# tinyduino-breakout-mk-4_0.net
KiCad netlist of a schematic drawn in EAGLE
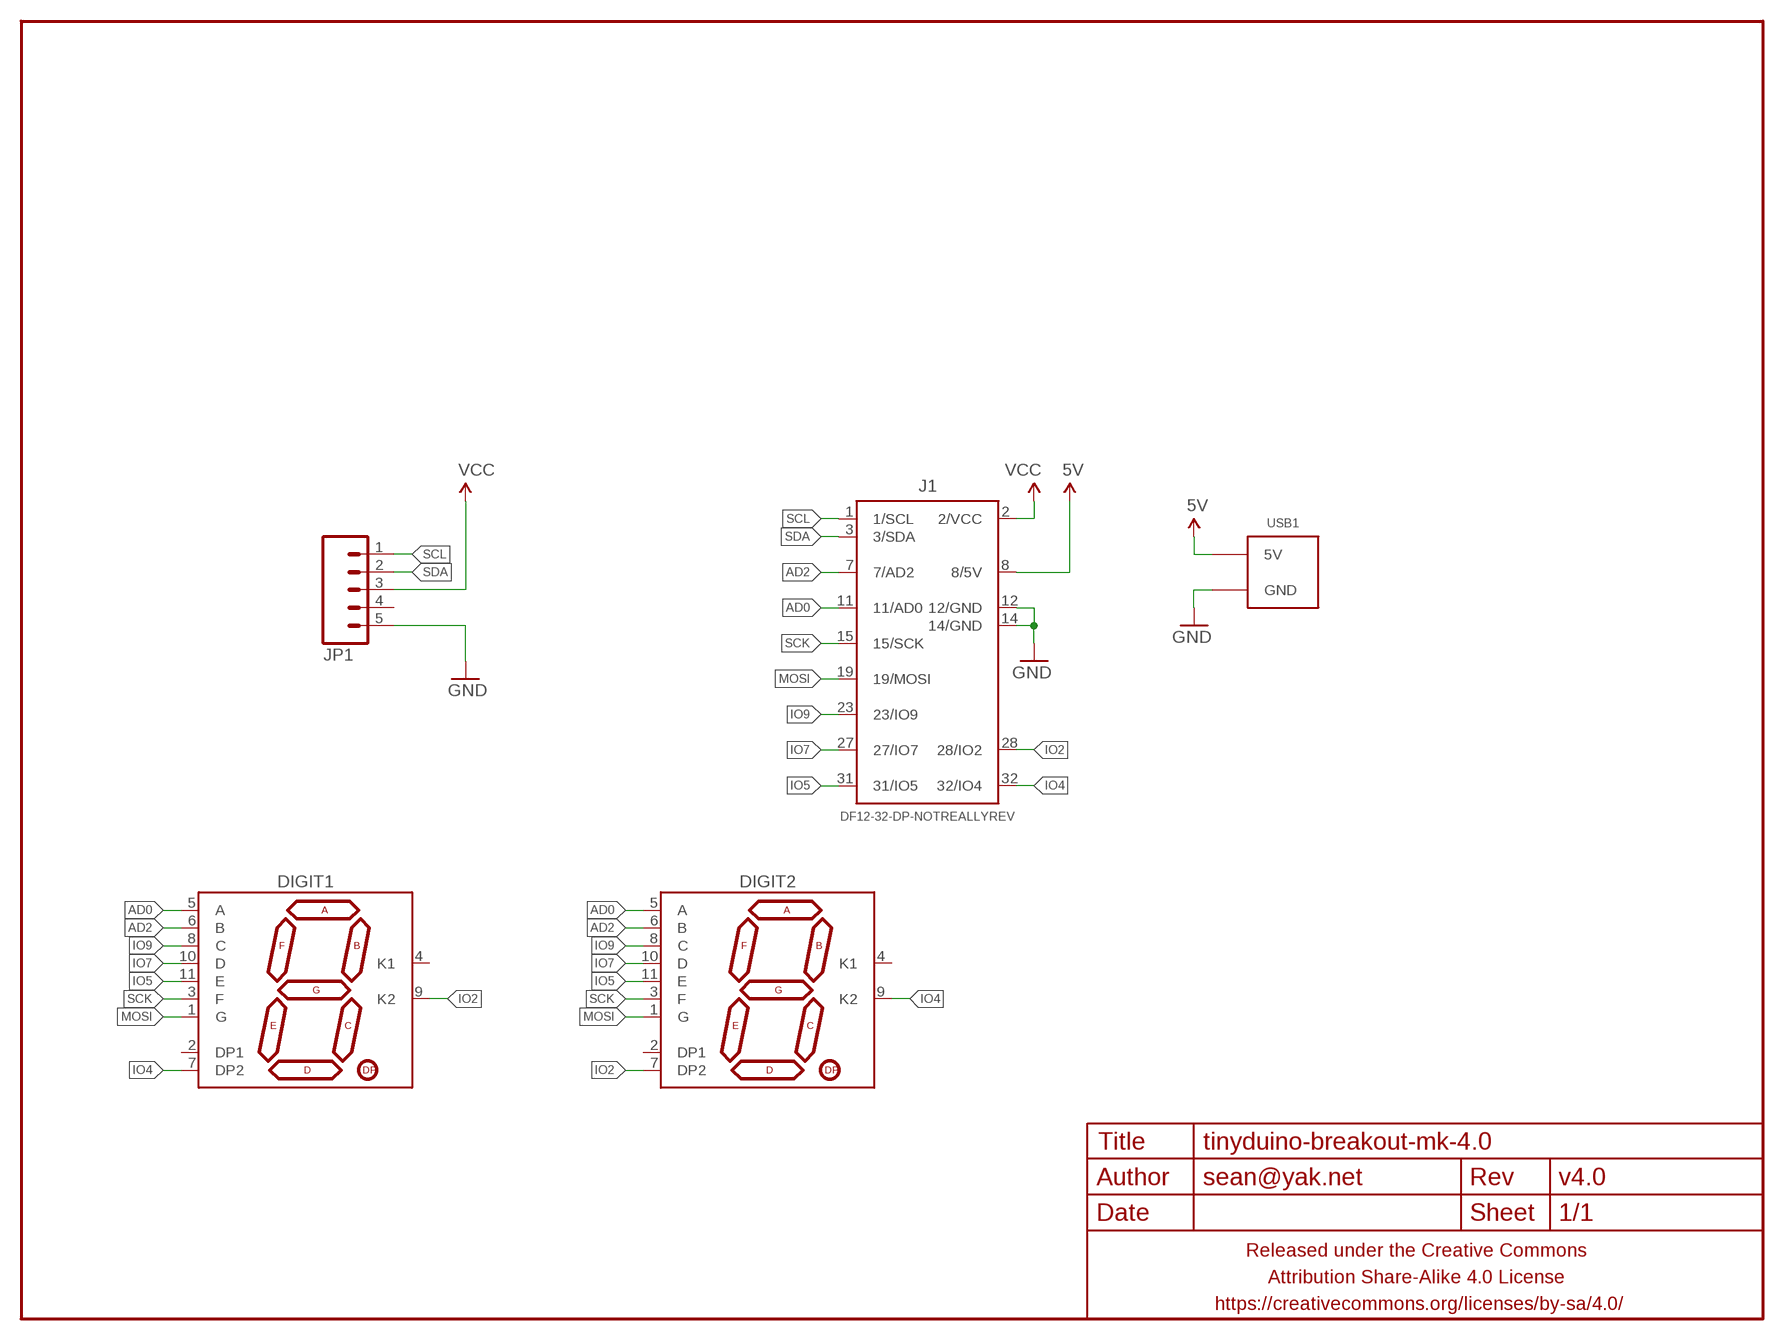
[diagram p0: schematic, sheet 1]

(export (version "E")
  (design (tool "Eeschema 10.0.6"))
  (components
    (comp (ref "DIGIT1")
      (value "7SEG_1DIG_2DP7MM_CC_SMT")
      (footprint "eagle-import:7SEG_1DIG_7MM_SMT")
      (libsource (lib "eagle-import") (part "7SEG_1DIG_2DP7MM_CC_SMT"))
    )
    (comp (ref "DIGIT2")
      (value "7SEG_1DIG_2DP7MM_CC_SMT")
      (footprint "eagle-import:7SEG_1DIG_7MM_SMT")
      (libsource (lib "eagle-import") (part "7SEG_1DIG_2DP7MM_CC_SMT"))
    )
    (comp (ref "FRAME1")
      (value "FRAME-LETTERNO_PACKAGE")
      (footprint "eagle-import:DUMMY")
      (fields (field (name "DESIGNER") "sean@yak.net") (field (name "VERSION") "v4.0"))
      (libsource (lib "eagle-import") (part "FRAME-LETTERNO_PACKAGE"))
    )
    (comp (ref "J1")
      (value "DF12-32-DP-NOTREALLYREV")
      (footprint "eagle-import:DF12-32-DP-I2C+EXTRA-REV")
      (libsource (lib "eagle-import") (part "DF12-32-DP-NOTREALLYREV"))
    )
    (comp (ref "JP1")
      (value "M05PTH-CENTERED")
      (footprint "eagle-import:1X05_PTH_CENTERED")
      (libsource (lib "eagle-import") (part "M05PTH-CENTERED"))
    )
    (comp (ref "USB1")
      (value "USB_AB_PWRONLY")
      (footprint "eagle-import:FCI-10103594-USB-MICRO-B-PWRONLY")
      (libsource (lib "eagle-import") (part "USB_AB_PWRONLY"))
    )
  )
  (nets
    (net (code "1") (name "5V") (class "Default")
      (node (ref "J1") (pin "8") (pinfunction "8/5V_8") (pintype "bidirectional"))
      (node (ref "USB1") (pin "1") (pinfunction "5V_1") (pintype "bidirectional"))
    )
    (net (code "2") (name "AD0") (class "Default")
      (node (ref "DIGIT1") (pin "5") (pinfunction "A_5") (pintype "bidirectional"))
      (node (ref "DIGIT2") (pin "5") (pinfunction "A_5") (pintype "bidirectional"))
      (node (ref "J1") (pin "11") (pinfunction "11/AD0_11") (pintype "bidirectional"))
    )
    (net (code "3") (name "AD2") (class "Default")
      (node (ref "DIGIT1") (pin "6") (pinfunction "B_6") (pintype "bidirectional"))
      (node (ref "DIGIT2") (pin "6") (pinfunction "B_6") (pintype "bidirectional"))
      (node (ref "J1") (pin "7") (pinfunction "7/AD2_7") (pintype "bidirectional"))
    )
    (net (code "4") (name "GND") (class "Default")
      (node (ref "J1") (pin "12") (pinfunction "12/GND_12") (pintype "bidirectional"))
      (node (ref "J1") (pin "14") (pinfunction "14/GND_14") (pintype "bidirectional"))
      (node (ref "JP1") (pin "5") (pinfunction "5_5") (pintype "passive"))
      (node (ref "USB1") (pin "5") (pinfunction "GND_5") (pintype "bidirectional"))
      (node (ref "USB1") (pin "SHIELD@1") (pinfunction "GND_SHIELD@1") (pintype "bidirectional"))
      (node (ref "USB1") (pin "SHIELD@2") (pinfunction "GND_SHIELD@2") (pintype "bidirectional"))
      (node (ref "USB1") (pin "SHIELD@3") (pinfunction "GND_SHIELD@3") (pintype "bidirectional"))
      (node (ref "USB1") (pin "SHIELD@4") (pinfunction "GND_SHIELD@4") (pintype "bidirectional"))
    )
    (net (code "5") (name "IO2") (class "Default")
      (node (ref "DIGIT1") (pin "9") (pinfunction "K2_9") (pintype "bidirectional"))
      (node (ref "DIGIT2") (pin "7") (pinfunction "DP2_7") (pintype "bidirectional"))
      (node (ref "J1") (pin "28") (pinfunction "28/IO2_28") (pintype "bidirectional"))
    )
    (net (code "6") (name "IO4") (class "Default")
      (node (ref "DIGIT1") (pin "7") (pinfunction "DP2_7") (pintype "bidirectional"))
      (node (ref "DIGIT2") (pin "9") (pinfunction "K2_9") (pintype "bidirectional"))
      (node (ref "J1") (pin "32") (pinfunction "32/IO4_32") (pintype "bidirectional"))
    )
    (net (code "7") (name "IO5") (class "Default")
      (node (ref "DIGIT1") (pin "11") (pinfunction "E_11") (pintype "bidirectional"))
      (node (ref "DIGIT2") (pin "11") (pinfunction "E_11") (pintype "bidirectional"))
      (node (ref "J1") (pin "31") (pinfunction "31/IO5_31") (pintype "bidirectional"))
    )
    (net (code "8") (name "IO7") (class "Default")
      (node (ref "DIGIT1") (pin "10") (pinfunction "D_10") (pintype "bidirectional"))
      (node (ref "DIGIT2") (pin "10") (pinfunction "D_10") (pintype "bidirectional"))
      (node (ref "J1") (pin "27") (pinfunction "27/IO7_27") (pintype "bidirectional"))
    )
    (net (code "9") (name "IO9") (class "Default")
      (node (ref "DIGIT1") (pin "8") (pinfunction "C_8") (pintype "bidirectional"))
      (node (ref "DIGIT2") (pin "8") (pinfunction "C_8") (pintype "bidirectional"))
      (node (ref "J1") (pin "23") (pinfunction "23/IO9_23") (pintype "bidirectional"))
    )
    (net (code "10") (name "MOSI") (class "Default")
      (node (ref "DIGIT1") (pin "1") (pinfunction "G_1") (pintype "bidirectional"))
      (node (ref "DIGIT2") (pin "1") (pinfunction "G_1") (pintype "bidirectional"))
      (node (ref "J1") (pin "19") (pinfunction "19/MOSI_19") (pintype "bidirectional"))
    )
    (net (code "11") (name "SCK") (class "Default")
      (node (ref "DIGIT1") (pin "3") (pinfunction "F_3") (pintype "bidirectional"))
      (node (ref "DIGIT2") (pin "3") (pinfunction "F_3") (pintype "bidirectional"))
      (node (ref "J1") (pin "15") (pinfunction "15/SCK_15") (pintype "bidirectional"))
    )
    (net (code "12") (name "SCL") (class "Default")
      (node (ref "J1") (pin "1") (pinfunction "1/SCL_1") (pintype "bidirectional"))
      (node (ref "JP1") (pin "1") (pinfunction "1_1") (pintype "passive"))
    )
    (net (code "13") (name "SDA") (class "Default")
      (node (ref "J1") (pin "3") (pinfunction "3/SDA_3") (pintype "bidirectional"))
      (node (ref "JP1") (pin "2") (pinfunction "2_2") (pintype "passive"))
    )
    (net (code "14") (name "VCC") (class "Default")
      (node (ref "J1") (pin "2") (pinfunction "2/VCC_2") (pintype "bidirectional"))
      (node (ref "JP1") (pin "3") (pinfunction "3_3") (pintype "passive"))
    )
    (net (code "15") (name "unconnected-(DIGIT1-DP1-Pad2)") (class "Default")
      (node (ref "DIGIT1") (pin "2") (pinfunction "DP1_2") (pintype "bidirectional"))
    )
    (net (code "16") (name "unconnected-(DIGIT1-K1-Pad4)") (class "Default")
      (node (ref "DIGIT1") (pin "4") (pinfunction "K1_4") (pintype "bidirectional"))
    )
    (net (code "17") (name "unconnected-(DIGIT2-DP1-Pad2)") (class "Default")
      (node (ref "DIGIT2") (pin "2") (pinfunction "DP1_2") (pintype "bidirectional"))
    )
    (net (code "18") (name "unconnected-(DIGIT2-K1-Pad4)") (class "Default")
      (node (ref "DIGIT2") (pin "4") (pinfunction "K1_4") (pintype "bidirectional"))
    )
    (net (code "19") (name "unconnected-(JP1-Pad4)") (class "Default")
      (node (ref "JP1") (pin "4") (pinfunction "4_4") (pintype "passive"))
    )
  )
)
